# ESP8266.net
KiCad netlist of a schematic drawn in EAGLE
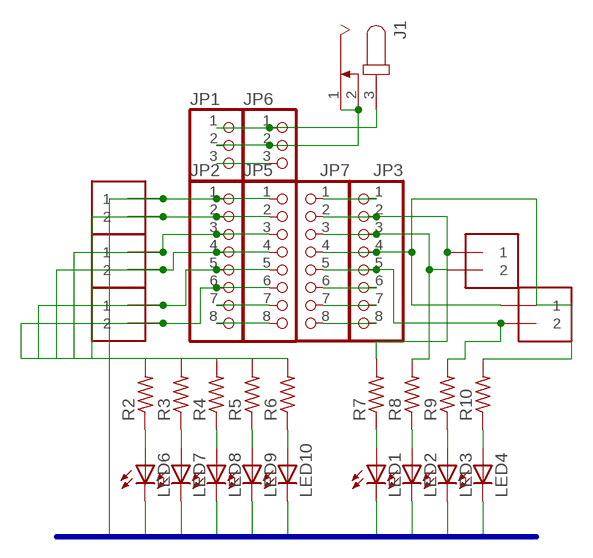
[diagram p0: schematic, sheet 1]

(export (version "E")
  (design (tool "Eeschema 10.0.6"))
  (components
    (comp (ref "J1")
      (value "JACK-PLUG0")
      (footprint "eagle-import:SPC4077")
      (libsource (lib "eagle-import") (part "JACK-PLUG0"))
    )
    (comp (ref "J2")
      (value "1X2-3.5MM")
      (footprint "eagle-import:1X2-3.5MM")
      (libsource (lib "eagle-import") (part "1X2-3.5MM"))
    )
    (comp (ref "J3")
      (value "1X2-3.5MM")
      (footprint "eagle-import:1X2-3.5MM")
      (libsource (lib "eagle-import") (part "1X2-3.5MM"))
    )
    (comp (ref "J4")
      (value "1X2-3.5MM")
      (footprint "eagle-import:1X2-3.5MM")
      (libsource (lib "eagle-import") (part "1X2-3.5MM"))
    )
    (comp (ref "J7")
      (value "1X2-3.5MM")
      (footprint "eagle-import:1X2-3.5MM")
      (libsource (lib "eagle-import") (part "1X2-3.5MM"))
    )
    (comp (ref "J8")
      (value "1X2-3.5MM")
      (footprint "eagle-import:1X2-3.5MM")
      (libsource (lib "eagle-import") (part "1X2-3.5MM"))
    )
    (comp (ref "JP1")
      (value "PINHD-1X3")
      (footprint "eagle-import:1X03")
      (libsource (lib "eagle-import") (part "PINHD-1X3"))
    )
    (comp (ref "JP2")
      (value "PINHD-1X8BIG")
      (footprint "eagle-import:1X08-BIG")
      (libsource (lib "eagle-import") (part "PINHD-1X8BIG"))
    )
    (comp (ref "JP3")
      (value "PINHD-1X8BIG")
      (footprint "eagle-import:1X08-BIG")
      (libsource (lib "eagle-import") (part "PINHD-1X8BIG"))
    )
    (comp (ref "JP5")
      (value "PINHD-1X8BIG")
      (footprint "eagle-import:1X08-BIG")
      (libsource (lib "eagle-import") (part "PINHD-1X8BIG"))
    )
    (comp (ref "JP6")
      (value "PINHD-1X3")
      (footprint "eagle-import:1X03")
      (libsource (lib "eagle-import") (part "PINHD-1X3"))
    )
    (comp (ref "JP7")
      (value "PINHD-1X8BIG")
      (footprint "eagle-import:1X08-BIG")
      (libsource (lib "eagle-import") (part "PINHD-1X8BIG"))
    )
    (comp (ref "LED1")
      (value "LEDCHIP-LED0805")
      (footprint "eagle-import:CHIP-LED0805")
      (libsource (lib "eagle-import") (part "LEDCHIP-LED0805"))
    )
    (comp (ref "LED2")
      (value "LEDCHIP-LED0805")
      (footprint "eagle-import:CHIP-LED0805")
      (libsource (lib "eagle-import") (part "LEDCHIP-LED0805"))
    )
    (comp (ref "LED3")
      (value "LEDCHIP-LED0805")
      (footprint "eagle-import:CHIP-LED0805")
      (libsource (lib "eagle-import") (part "LEDCHIP-LED0805"))
    )
    (comp (ref "LED4")
      (value "LEDCHIP-LED0805")
      (footprint "eagle-import:CHIP-LED0805")
      (libsource (lib "eagle-import") (part "LEDCHIP-LED0805"))
    )
    (comp (ref "LED6")
      (value "LEDCHIP-LED0805")
      (footprint "eagle-import:CHIP-LED0805")
      (libsource (lib "eagle-import") (part "LEDCHIP-LED0805"))
    )
    (comp (ref "LED7")
      (value "LEDCHIP-LED0805")
      (footprint "eagle-import:CHIP-LED0805")
      (libsource (lib "eagle-import") (part "LEDCHIP-LED0805"))
    )
    (comp (ref "LED8")
      (value "LEDCHIP-LED0805")
      (footprint "eagle-import:CHIP-LED0805")
      (libsource (lib "eagle-import") (part "LEDCHIP-LED0805"))
    )
    (comp (ref "LED9")
      (value "LEDCHIP-LED0805")
      (footprint "eagle-import:CHIP-LED0805")
      (libsource (lib "eagle-import") (part "LEDCHIP-LED0805"))
    )
    (comp (ref "LED10")
      (value "LEDCHIP-LED0805")
      (footprint "eagle-import:CHIP-LED0805")
      (libsource (lib "eagle-import") (part "LEDCHIP-LED0805"))
    )
    (comp (ref "R2")
      (value "R-US_R0805")
      (footprint "eagle-import:R0805")
      (libsource (lib "eagle-import") (part "R-US_R0805"))
    )
    (comp (ref "R3")
      (value "R-US_R0805")
      (footprint "eagle-import:R0805")
      (libsource (lib "eagle-import") (part "R-US_R0805"))
    )
    (comp (ref "R4")
      (value "R-US_R0805")
      (footprint "eagle-import:R0805")
      (libsource (lib "eagle-import") (part "R-US_R0805"))
    )
    (comp (ref "R5")
      (value "R-US_R0805")
      (footprint "eagle-import:R0805")
      (libsource (lib "eagle-import") (part "R-US_R0805"))
    )
    (comp (ref "R6")
      (value "R-US_R0805")
      (footprint "eagle-import:R0805")
      (libsource (lib "eagle-import") (part "R-US_R0805"))
    )
    (comp (ref "R7")
      (value "R-US_R0805")
      (footprint "eagle-import:R0805")
      (libsource (lib "eagle-import") (part "R-US_R0805"))
    )
    (comp (ref "R8")
      (value "R-US_R0805")
      (footprint "eagle-import:R0805")
      (libsource (lib "eagle-import") (part "R-US_R0805"))
    )
    (comp (ref "R9")
      (value "R-US_R0805")
      (footprint "eagle-import:R0805")
      (libsource (lib "eagle-import") (part "R-US_R0805"))
    )
    (comp (ref "R10")
      (value "R-US_R0805")
      (footprint "eagle-import:R0805")
      (libsource (lib "eagle-import") (part "R-US_R0805"))
    )
  )
  (nets
    (net (code "1") (name "/GND") (class "Default")
      (node (ref "J1") (pin "1") (pinfunction "1_1") (pintype "passive"))
      (node (ref "J1") (pin "2") (pinfunction "2_2") (pintype "passive"))
      (node (ref "J2") (pin "1") (pinfunction "1_1") (pintype "passive"))
      (node (ref "JP1") (pin "2") (pinfunction "2_2") (pintype "passive"))
      (node (ref "JP2") (pin "1") (pinfunction "1_1") (pintype "passive"))
      (node (ref "JP5") (pin "1") (pinfunction "1_1") (pintype "passive"))
      (node (ref "JP6") (pin "2") (pinfunction "2_2") (pintype "passive"))
      (node (ref "LED1") (pin "C") (pinfunction "C_C") (pintype "passive"))
      (node (ref "LED10") (pin "C") (pinfunction "C_C") (pintype "passive"))
      (node (ref "LED2") (pin "C") (pinfunction "C_C") (pintype "passive"))
      (node (ref "LED3") (pin "C") (pinfunction "C_C") (pintype "passive"))
      (node (ref "LED4") (pin "C") (pinfunction "C_C") (pintype "passive"))
      (node (ref "LED6") (pin "C") (pinfunction "C_C") (pintype "passive"))
      (node (ref "LED7") (pin "C") (pinfunction "C_C") (pintype "passive"))
      (node (ref "LED8") (pin "C") (pinfunction "C_C") (pintype "passive"))
      (node (ref "LED9") (pin "C") (pinfunction "C_C") (pintype "passive"))
    )
    (net (code "2") (name "Net-(J1-Pad3)") (class "Default")
      (node (ref "J1") (pin "3") (pinfunction "3_3") (pintype "passive"))
      (node (ref "JP1") (pin "1") (pinfunction "1_1") (pintype "passive"))
      (node (ref "JP6") (pin "1") (pinfunction "1_1") (pintype "passive"))
    )
    (net (code "3") (name "Net-(J2-Pad2)") (class "Default")
      (node (ref "J2") (pin "2") (pinfunction "2_2") (pintype "passive"))
      (node (ref "JP2") (pin "2") (pinfunction "2_2") (pintype "passive"))
      (node (ref "JP5") (pin "2") (pinfunction "2_2") (pintype "passive"))
      (node (ref "R2") (pin "2") (pinfunction "2_2") (pintype "passive"))
    )
    (net (code "4") (name "Net-(J3-Pad1)") (class "Default")
      (node (ref "J3") (pin "1") (pinfunction "1_1") (pintype "passive"))
      (node (ref "JP2") (pin "3") (pinfunction "3_3") (pintype "passive"))
      (node (ref "JP5") (pin "3") (pinfunction "3_3") (pintype "passive"))
      (node (ref "R3") (pin "2") (pinfunction "2_2") (pintype "passive"))
    )
    (net (code "5") (name "Net-(J3-Pad2)") (class "Default")
      (node (ref "J3") (pin "2") (pinfunction "2_2") (pintype "passive"))
      (node (ref "JP2") (pin "4") (pinfunction "4_4") (pintype "passive"))
      (node (ref "JP5") (pin "4") (pinfunction "4_4") (pintype "passive"))
      (node (ref "R4") (pin "2") (pinfunction "2_2") (pintype "passive"))
    )
    (net (code "6") (name "Net-(J4-Pad1)") (class "Default")
      (node (ref "J4") (pin "1") (pinfunction "1_1") (pintype "passive"))
      (node (ref "JP2") (pin "5") (pinfunction "5_5") (pintype "passive"))
      (node (ref "JP5") (pin "5") (pinfunction "5_5") (pintype "passive"))
      (node (ref "R5") (pin "2") (pinfunction "2_2") (pintype "passive"))
    )
    (net (code "7") (name "Net-(J4-Pad2)") (class "Default")
      (node (ref "J4") (pin "2") (pinfunction "2_2") (pintype "passive"))
      (node (ref "JP2") (pin "6") (pinfunction "6_6") (pintype "passive"))
      (node (ref "JP5") (pin "6") (pinfunction "6_6") (pintype "passive"))
      (node (ref "R6") (pin "2") (pinfunction "2_2") (pintype "passive"))
    )
    (net (code "8") (name "Net-(J7-Pad1)") (class "Default")
      (node (ref "J7") (pin "1") (pinfunction "1_1") (pintype "passive"))
      (node (ref "JP3") (pin "2") (pinfunction "2_2") (pintype "passive"))
      (node (ref "JP7") (pin "2") (pinfunction "2_2") (pintype "passive"))
      (node (ref "R7") (pin "2") (pinfunction "2_2") (pintype "passive"))
    )
    (net (code "9") (name "Net-(J7-Pad2)") (class "Default")
      (node (ref "J7") (pin "2") (pinfunction "2_2") (pintype "passive"))
      (node (ref "JP3") (pin "3") (pinfunction "3_3") (pintype "passive"))
      (node (ref "JP7") (pin "3") (pinfunction "3_3") (pintype "passive"))
      (node (ref "R8") (pin "2") (pinfunction "2_2") (pintype "passive"))
    )
    (net (code "10") (name "Net-(J8-Pad1)") (class "Default")
      (node (ref "J8") (pin "1") (pinfunction "1_1") (pintype "passive"))
      (node (ref "JP3") (pin "4") (pinfunction "4_4") (pintype "passive"))
      (node (ref "JP7") (pin "4") (pinfunction "4_4") (pintype "passive"))
      (node (ref "R10") (pin "2") (pinfunction "2_2") (pintype "passive"))
    )
    (net (code "11") (name "Net-(J8-Pad2)") (class "Default")
      (node (ref "J8") (pin "2") (pinfunction "2_2") (pintype "passive"))
      (node (ref "JP3") (pin "5") (pinfunction "5_5") (pintype "passive"))
      (node (ref "JP7") (pin "5") (pinfunction "5_5") (pintype "passive"))
      (node (ref "R9") (pin "2") (pinfunction "2_2") (pintype "passive"))
    )
    (net (code "12") (name "Net-(JP1-Pad3)") (class "Default")
      (node (ref "JP1") (pin "3") (pinfunction "3_3") (pintype "passive"))
      (node (ref "JP6") (pin "3") (pinfunction "3_3") (pintype "passive"))
    )
    (net (code "13") (name "Net-(JP2-Pad7)") (class "Default")
      (node (ref "JP2") (pin "7") (pinfunction "7_7") (pintype "passive"))
      (node (ref "JP5") (pin "7") (pinfunction "7_7") (pintype "passive"))
    )
    (net (code "14") (name "Net-(JP2-Pad8)") (class "Default")
      (node (ref "JP2") (pin "8") (pinfunction "8_8") (pintype "passive"))
      (node (ref "JP5") (pin "8") (pinfunction "8_8") (pintype "passive"))
    )
    (net (code "15") (name "Net-(JP3-Pad1)") (class "Default")
      (node (ref "JP3") (pin "1") (pinfunction "1_1") (pintype "passive"))
      (node (ref "JP7") (pin "1") (pinfunction "1_1") (pintype "passive"))
    )
    (net (code "16") (name "Net-(JP3-Pad6)") (class "Default")
      (node (ref "JP3") (pin "6") (pinfunction "6_6") (pintype "passive"))
      (node (ref "JP7") (pin "6") (pinfunction "6_6") (pintype "passive"))
    )
    (net (code "17") (name "Net-(JP3-Pad7)") (class "Default")
      (node (ref "JP3") (pin "7") (pinfunction "7_7") (pintype "passive"))
      (node (ref "JP7") (pin "7") (pinfunction "7_7") (pintype "passive"))
    )
    (net (code "18") (name "Net-(JP3-Pad8)") (class "Default")
      (node (ref "JP3") (pin "8") (pinfunction "8_8") (pintype "passive"))
      (node (ref "JP7") (pin "8") (pinfunction "8_8") (pintype "passive"))
    )
    (net (code "19") (name "Net-(LED1-PadA)") (class "Default")
      (node (ref "LED1") (pin "A") (pinfunction "A_A") (pintype "passive"))
      (node (ref "R7") (pin "1") (pinfunction "1_1") (pintype "passive"))
    )
    (net (code "20") (name "Net-(LED2-PadA)") (class "Default")
      (node (ref "LED2") (pin "A") (pinfunction "A_A") (pintype "passive"))
      (node (ref "R8") (pin "1") (pinfunction "1_1") (pintype "passive"))
    )
    (net (code "21") (name "Net-(LED3-PadA)") (class "Default")
      (node (ref "LED3") (pin "A") (pinfunction "A_A") (pintype "passive"))
      (node (ref "R9") (pin "1") (pinfunction "1_1") (pintype "passive"))
    )
    (net (code "22") (name "Net-(LED4-PadA)") (class "Default")
      (node (ref "LED4") (pin "A") (pinfunction "A_A") (pintype "passive"))
      (node (ref "R10") (pin "1") (pinfunction "1_1") (pintype "passive"))
    )
    (net (code "23") (name "Net-(LED6-PadA)") (class "Default")
      (node (ref "LED6") (pin "A") (pinfunction "A_A") (pintype "passive"))
      (node (ref "R2") (pin "1") (pinfunction "1_1") (pintype "passive"))
    )
    (net (code "24") (name "Net-(LED7-PadA)") (class "Default")
      (node (ref "LED7") (pin "A") (pinfunction "A_A") (pintype "passive"))
      (node (ref "R3") (pin "1") (pinfunction "1_1") (pintype "passive"))
    )
    (net (code "25") (name "Net-(LED8-PadA)") (class "Default")
      (node (ref "LED8") (pin "A") (pinfunction "A_A") (pintype "passive"))
      (node (ref "R4") (pin "1") (pinfunction "1_1") (pintype "passive"))
    )
    (net (code "26") (name "Net-(LED9-PadA)") (class "Default")
      (node (ref "LED9") (pin "A") (pinfunction "A_A") (pintype "passive"))
      (node (ref "R5") (pin "1") (pinfunction "1_1") (pintype "passive"))
    )
    (net (code "27") (name "Net-(LED10-PadA)") (class "Default")
      (node (ref "LED10") (pin "A") (pinfunction "A_A") (pintype "passive"))
      (node (ref "R6") (pin "1") (pinfunction "1_1") (pintype "passive"))
    )
  )
)
